# Sheet2.net
KiCad netlist of a schematic drawn in Altium Designer
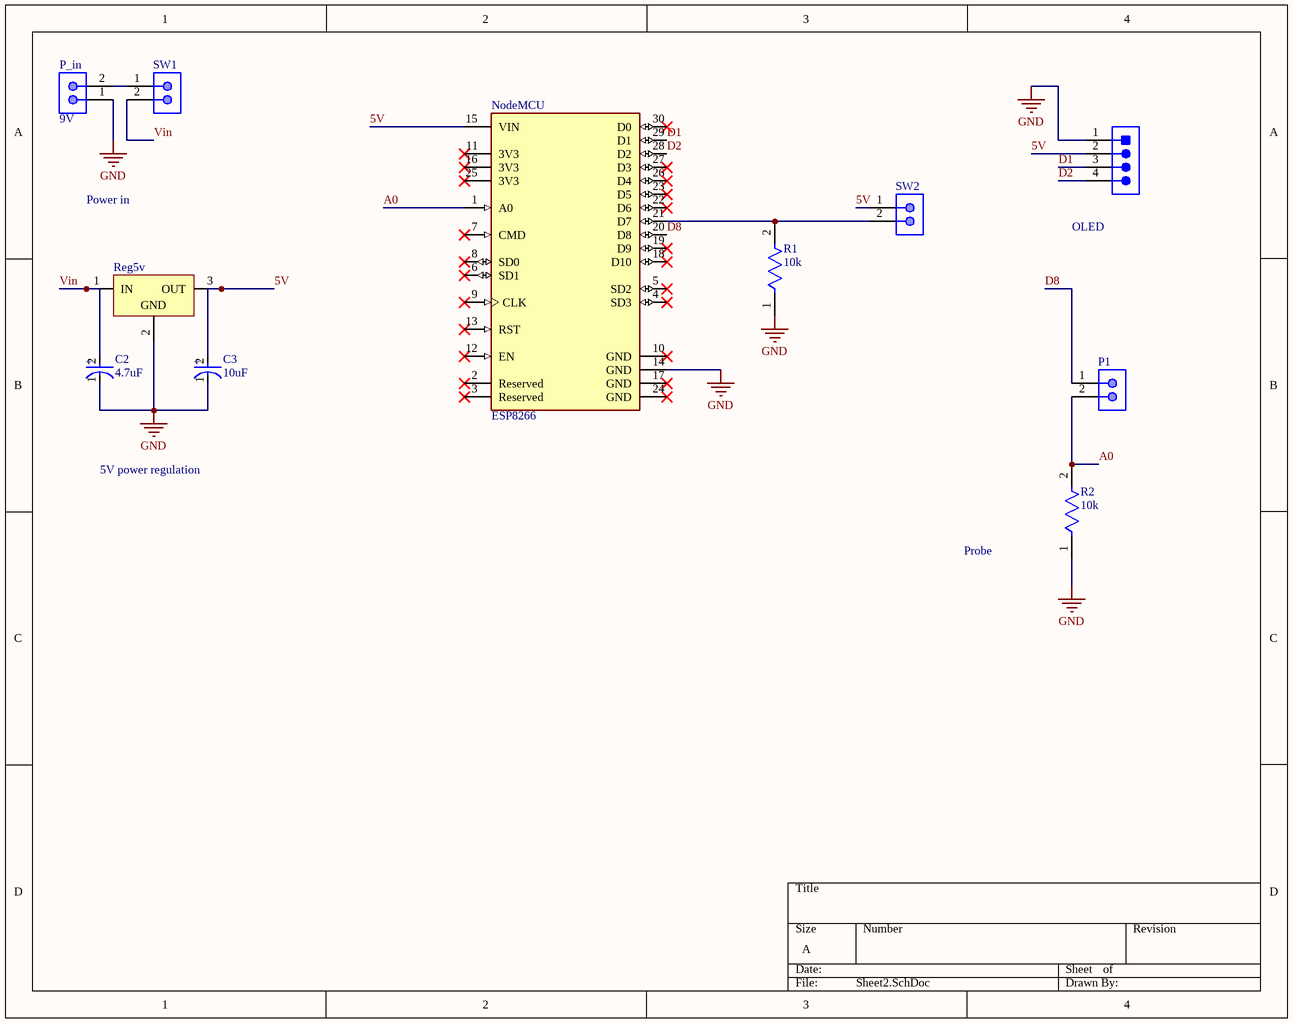
[diagram p0: Sheet2.SchDoc]

(export (version "E")
  (design (tool "Eeschema 10.0.6"))
  (components
    (comp (ref "C2")
      (value "4.7uF")
      (footprint "FP-RAD-TH-D_6_3_0_5-L_11-MFG")
      (description "Aluminum Electrolytic Capacitors (Radial Lead Type) 4.7uF ±20% 160V")
      (fields (field (name "VOLTAGE") "160V") (field (name "TOLERANCE") "20%"))
      (libsource (lib "Altium Content Vault") (part "203bc49f2ac43e59fd269a8c329ed05"))
    )
    (comp (ref "C3")
      (value "10uF")
      (footprint "FP-RAD-TH-D_5_0_5-L_11_1-MFG")
      (description "Aluminum Electrolytic Capacitors (Radial Lead Type) 10uF ±20% 100V")
      (fields (field (name "VOLTAGE") "100V") (field (name "TOLERANCE") "20%"))
      (libsource (lib "Altium Content Vault") (part "a00bbbee19879c290e62620ae7e47b1"))
    )
    (comp (ref "NodeMCU")
      (value "ESP8266")
      (footprint "FP-113990105-MFG")
      (description "NODEMCU V2 LUA BASED ESP8266 DEV")
      (fields
        (field (name "MANUFACTURER") "Seeed Studio")
        (field (name "MANUFACTURER PART NUMBER") "113990105")
      )
      (libsource (lib "dewameter 2.0") (part "CMP-138991-000001-1"))
    )
    (comp (ref "OLED")
      (value "6")
      (footprint "TECO-640456-4")
      (description "Male Header, Pitch 2.54 mm, 1 x 4 Position, Height 10.03 mm, Tail Length 3.56 mm, RoHS, Bulk")
      (fields
        (field (name "MANUFACTURER") "TE Connectivity")
        (field (name "MANUFACTURER PART NUMBER") "640456-4")
      )
      (libsource (lib "dewameter 2.0") (part "CMP-2000-05419-1"))
    )
    (comp (ref "P1")
      (value "5-146280-2")
      (footprint "TECO-5-146280-2_V")
      (fields (field (name "MANUFACTURER") "TE Connectivity"))
      (libsource (lib "Altium Content Vault") (part "CN-1P-M-R2"))
    )
    (comp (ref "P_in")
      (value "9V")
      (footprint "MOLX-22-27-2021_V")
      (fields (field (name "MANUFACTURER") "Molex") (field (name "PARTNUMBER") "0022272021"))
      (libsource (lib "") (part "CN-1P-M-R2_1"))
    )
    (comp (ref "R1")
      (value "10k")
      (footprint "FP-CF18-MFG")
      (description "RES 10K OHM 1/8W 5% CF AXIAL")
      (fields
        (field (name "MANUFACTURER PART NUMBER") "CF18JT10K0")
        (field (name "MANUFACTURER") "Stackpole Electronics")
      )
      (libsource (lib "Altium Content Vault") (part "1029c3af85768c4190bb7ad29bc67b5"))
    )
    (comp (ref "R2")
      (value "10k")
      (footprint "FP-CF18-MFG")
      (description "RES 10K OHM 1/8W 5% CF AXIAL")
      (fields
        (field (name "MANUFACTURER PART NUMBER") "CF18JT10K0")
        (field (name "MANUFACTURER") "Stackpole Electronics")
      )
      (libsource (lib "Altium Content Vault") (part "1029c3af85768c4190bb7ad29bc67b5"))
    )
    (comp (ref "Reg5v")
      (value "5V")
      (footprint "TO220")
      (description "Positive Voltage Regulator, 6V, 3-Pin TO-220")
      (libsource (lib "Altium Content Vault") (part "PM-REG-L4940-SIL3"))
    )
    (comp (ref "SW1")
      (value "5-146280-2")
      (footprint "TECO-5-146280-2_V")
      (fields (field (name "MANUFACTURER") "TE Connectivity"))
      (libsource (lib "Altium Content Vault") (part "CN-1P-M-R2"))
    )
    (comp (ref "SW2")
      (value "5-146280-2")
      (footprint "TECO-5-146280-2_V")
      (fields (field (name "MANUFACTURER") "TE Connectivity"))
      (libsource (lib "Altium Content Vault") (part "CN-1P-M-R2"))
    )
  )
  (nets
    (net (code "1") (name "/5V") (class "Default")
      (node (ref "C3") (pin "2") (pinfunction "A_2") (pintype "passive"))
      (node (ref "NodeMCU") (pin "15") (pinfunction "VIN_15") (pintype "power_in"))
      (node (ref "OLED") (pin "2") (pinfunction "2_2") (pintype "passive"))
      (node (ref "Reg5v") (pin "3") (pinfunction "OUT_3") (pintype "power_in"))
      (node (ref "SW2") (pin "1") (pinfunction "1_1") (pintype "passive"))
    )
    (net (code "2") (name "/A0") (class "Default")
      (node (ref "NodeMCU") (pin "1") (pinfunction "A0_1") (pintype "input"))
      (node (ref "P1") (pin "2") (pinfunction "2_2") (pintype "passive"))
      (node (ref "R2") (pin "2") (pinfunction "2_2") (pintype "passive"))
    )
    (net (code "3") (name "/D1") (class "Default")
      (node (ref "NodeMCU") (pin "29") (pinfunction "D1_29") (pintype "bidirectional"))
      (node (ref "OLED") (pin "3") (pinfunction "3_3") (pintype "passive"))
    )
    (net (code "4") (name "/D2") (class "Default")
      (node (ref "NodeMCU") (pin "28") (pinfunction "D2_28") (pintype "bidirectional"))
      (node (ref "OLED") (pin "4") (pinfunction "4_4") (pintype "passive"))
    )
    (net (code "5") (name "/D8") (class "Default")
      (node (ref "NodeMCU") (pin "20") (pinfunction "D8_20") (pintype "bidirectional"))
      (node (ref "P1") (pin "1") (pinfunction "1_1") (pintype "passive"))
    )
    (net (code "6") (name "/Vin") (class "Default")
      (node (ref "C2") (pin "2") (pinfunction "A_2") (pintype "passive"))
      (node (ref "Reg5v") (pin "1") (pinfunction "IN_1") (pintype "power_in"))
      (node (ref "SW1") (pin "2") (pinfunction "2_2") (pintype "passive"))
    )
    (net (code "7") (name "GND") (class "Default")
      (node (ref "C2") (pin "1") (pinfunction "C_1") (pintype "passive"))
      (node (ref "C3") (pin "1") (pinfunction "C_1") (pintype "passive"))
      (node (ref "NodeMCU") (pin "14") (pinfunction "GND_14") (pintype "power_in"))
      (node (ref "OLED") (pin "1") (pinfunction "1_1") (pintype "passive"))
      (node (ref "P_in") (pin "1") (pinfunction "1_1") (pintype "passive"))
      (node (ref "R1") (pin "1") (pinfunction "1_1") (pintype "passive"))
      (node (ref "R2") (pin "1") (pinfunction "1_1") (pintype "passive"))
      (node (ref "Reg5v") (pin "2") (pinfunction "GND_2") (pintype "power_in"))
    )
    (net (code "8") (name "Net-(NodeMCU-D7)") (class "Default")
      (node (ref "NodeMCU") (pin "21") (pinfunction "D7_21") (pintype "bidirectional"))
      (node (ref "R1") (pin "2") (pinfunction "2_2") (pintype "passive"))
      (node (ref "SW2") (pin "2") (pinfunction "2_2") (pintype "passive"))
    )
    (net (code "9") (name "Net-(P_in-Pad2)") (class "Default")
      (node (ref "P_in") (pin "2") (pinfunction "2_2") (pintype "passive"))
      (node (ref "SW1") (pin "1") (pinfunction "1_1") (pintype "passive"))
    )
    (net (code "10") (name "unconnected-(NodeMCU-3V3-Pad11)") (class "Default")
      (node (ref "NodeMCU") (pin "11") (pinfunction "3V3_11") (pintype "power_in+no_connect"))
    )
    (net (code "11") (name "unconnected-(NodeMCU-3V3-Pad16)") (class "Default")
      (node (ref "NodeMCU") (pin "16") (pinfunction "3V3_16") (pintype "power_in+no_connect"))
    )
    (net (code "12") (name "unconnected-(NodeMCU-3V3-Pad25)") (class "Default")
      (node (ref "NodeMCU") (pin "25") (pinfunction "3V3_25") (pintype "power_in+no_connect"))
    )
    (net (code "13") (name "unconnected-(NodeMCU-CLK-Pad9)") (class "Default")
      (node (ref "NodeMCU") (pin "9") (pinfunction "CLK_9") (pintype "input+no_connect"))
    )
    (net (code "14") (name "unconnected-(NodeMCU-CMD-Pad7)") (class "Default")
      (node (ref "NodeMCU") (pin "7") (pinfunction "CMD_7") (pintype "input+no_connect"))
    )
    (net (code "15") (name "unconnected-(NodeMCU-D0-Pad30)") (class "Default")
      (node (ref "NodeMCU") (pin "30") (pinfunction "D0_30") (pintype "bidirectional+no_connect"))
    )
    (net (code "16") (name "unconnected-(NodeMCU-D3-Pad27)") (class "Default")
      (node (ref "NodeMCU") (pin "27") (pinfunction "D3_27") (pintype "bidirectional+no_connect"))
    )
    (net (code "17") (name "unconnected-(NodeMCU-D4-Pad26)") (class "Default")
      (node (ref "NodeMCU") (pin "26") (pinfunction "D4_26") (pintype "bidirectional+no_connect"))
    )
    (net (code "18") (name "unconnected-(NodeMCU-D5-Pad23)") (class "Default")
      (node (ref "NodeMCU") (pin "23") (pinfunction "D5_23") (pintype "bidirectional+no_connect"))
    )
    (net (code "19") (name "unconnected-(NodeMCU-D6-Pad22)") (class "Default")
      (node (ref "NodeMCU") (pin "22") (pinfunction "D6_22") (pintype "bidirectional+no_connect"))
    )
    (net (code "20") (name "unconnected-(NodeMCU-D9-Pad19)") (class "Default")
      (node (ref "NodeMCU") (pin "19") (pinfunction "D9_19") (pintype "bidirectional+no_connect"))
    )
    (net (code "21") (name "unconnected-(NodeMCU-D10-Pad18)") (class "Default")
      (node (ref "NodeMCU") (pin "18") (pinfunction "D10_18") (pintype "bidirectional+no_connect"))
    )
    (net (code "22") (name "unconnected-(NodeMCU-EN-Pad12)") (class "Default")
      (node (ref "NodeMCU") (pin "12") (pinfunction "EN_12") (pintype "input+no_connect"))
    )
    (net (code "23") (name "unconnected-(NodeMCU-GND-Pad10)") (class "Default")
      (node (ref "NodeMCU") (pin "10") (pinfunction "GND_10") (pintype "power_in+no_connect"))
    )
    (net (code "24") (name "unconnected-(NodeMCU-GND-Pad17)") (class "Default")
      (node (ref "NodeMCU") (pin "17") (pinfunction "GND_17") (pintype "power_in+no_connect"))
    )
    (net (code "25") (name "unconnected-(NodeMCU-GND-Pad24)") (class "Default")
      (node (ref "NodeMCU") (pin "24") (pinfunction "GND_24") (pintype "power_in+no_connect"))
    )
    (net (code "26") (name "unconnected-(NodeMCU-RST-Pad13)") (class "Default")
      (node (ref "NodeMCU") (pin "13") (pinfunction "RST_13") (pintype "input+no_connect"))
    )
    (net (code "27") (name "unconnected-(NodeMCU-Reserved-Pad2)") (class "Default")
      (node (ref "NodeMCU") (pin "2") (pinfunction "Reserved_2") (pintype "passive+no_connect"))
    )
    (net (code "28") (name "unconnected-(NodeMCU-Reserved-Pad3)") (class "Default")
      (node (ref "NodeMCU") (pin "3") (pinfunction "Reserved_3") (pintype "passive+no_connect"))
    )
    (net (code "29") (name "unconnected-(NodeMCU-SD0-Pad8)") (class "Default")
      (node (ref "NodeMCU") (pin "8") (pinfunction "SD0_8") (pintype "bidirectional+no_connect"))
    )
    (net (code "30") (name "unconnected-(NodeMCU-SD1-Pad6)") (class "Default")
      (node (ref "NodeMCU") (pin "6") (pinfunction "SD1_6") (pintype "bidirectional+no_connect"))
    )
    (net (code "31") (name "unconnected-(NodeMCU-SD2-Pad5)") (class "Default")
      (node (ref "NodeMCU") (pin "5") (pinfunction "SD2_5") (pintype "bidirectional+no_connect"))
    )
    (net (code "32") (name "unconnected-(NodeMCU-SD3-Pad4)") (class "Default")
      (node (ref "NodeMCU") (pin "4") (pinfunction "SD3_4") (pintype "bidirectional+no_connect"))
    )
  )
)
